# Oven_Control.net
KiCad netlist of a schematic drawn in EAGLE
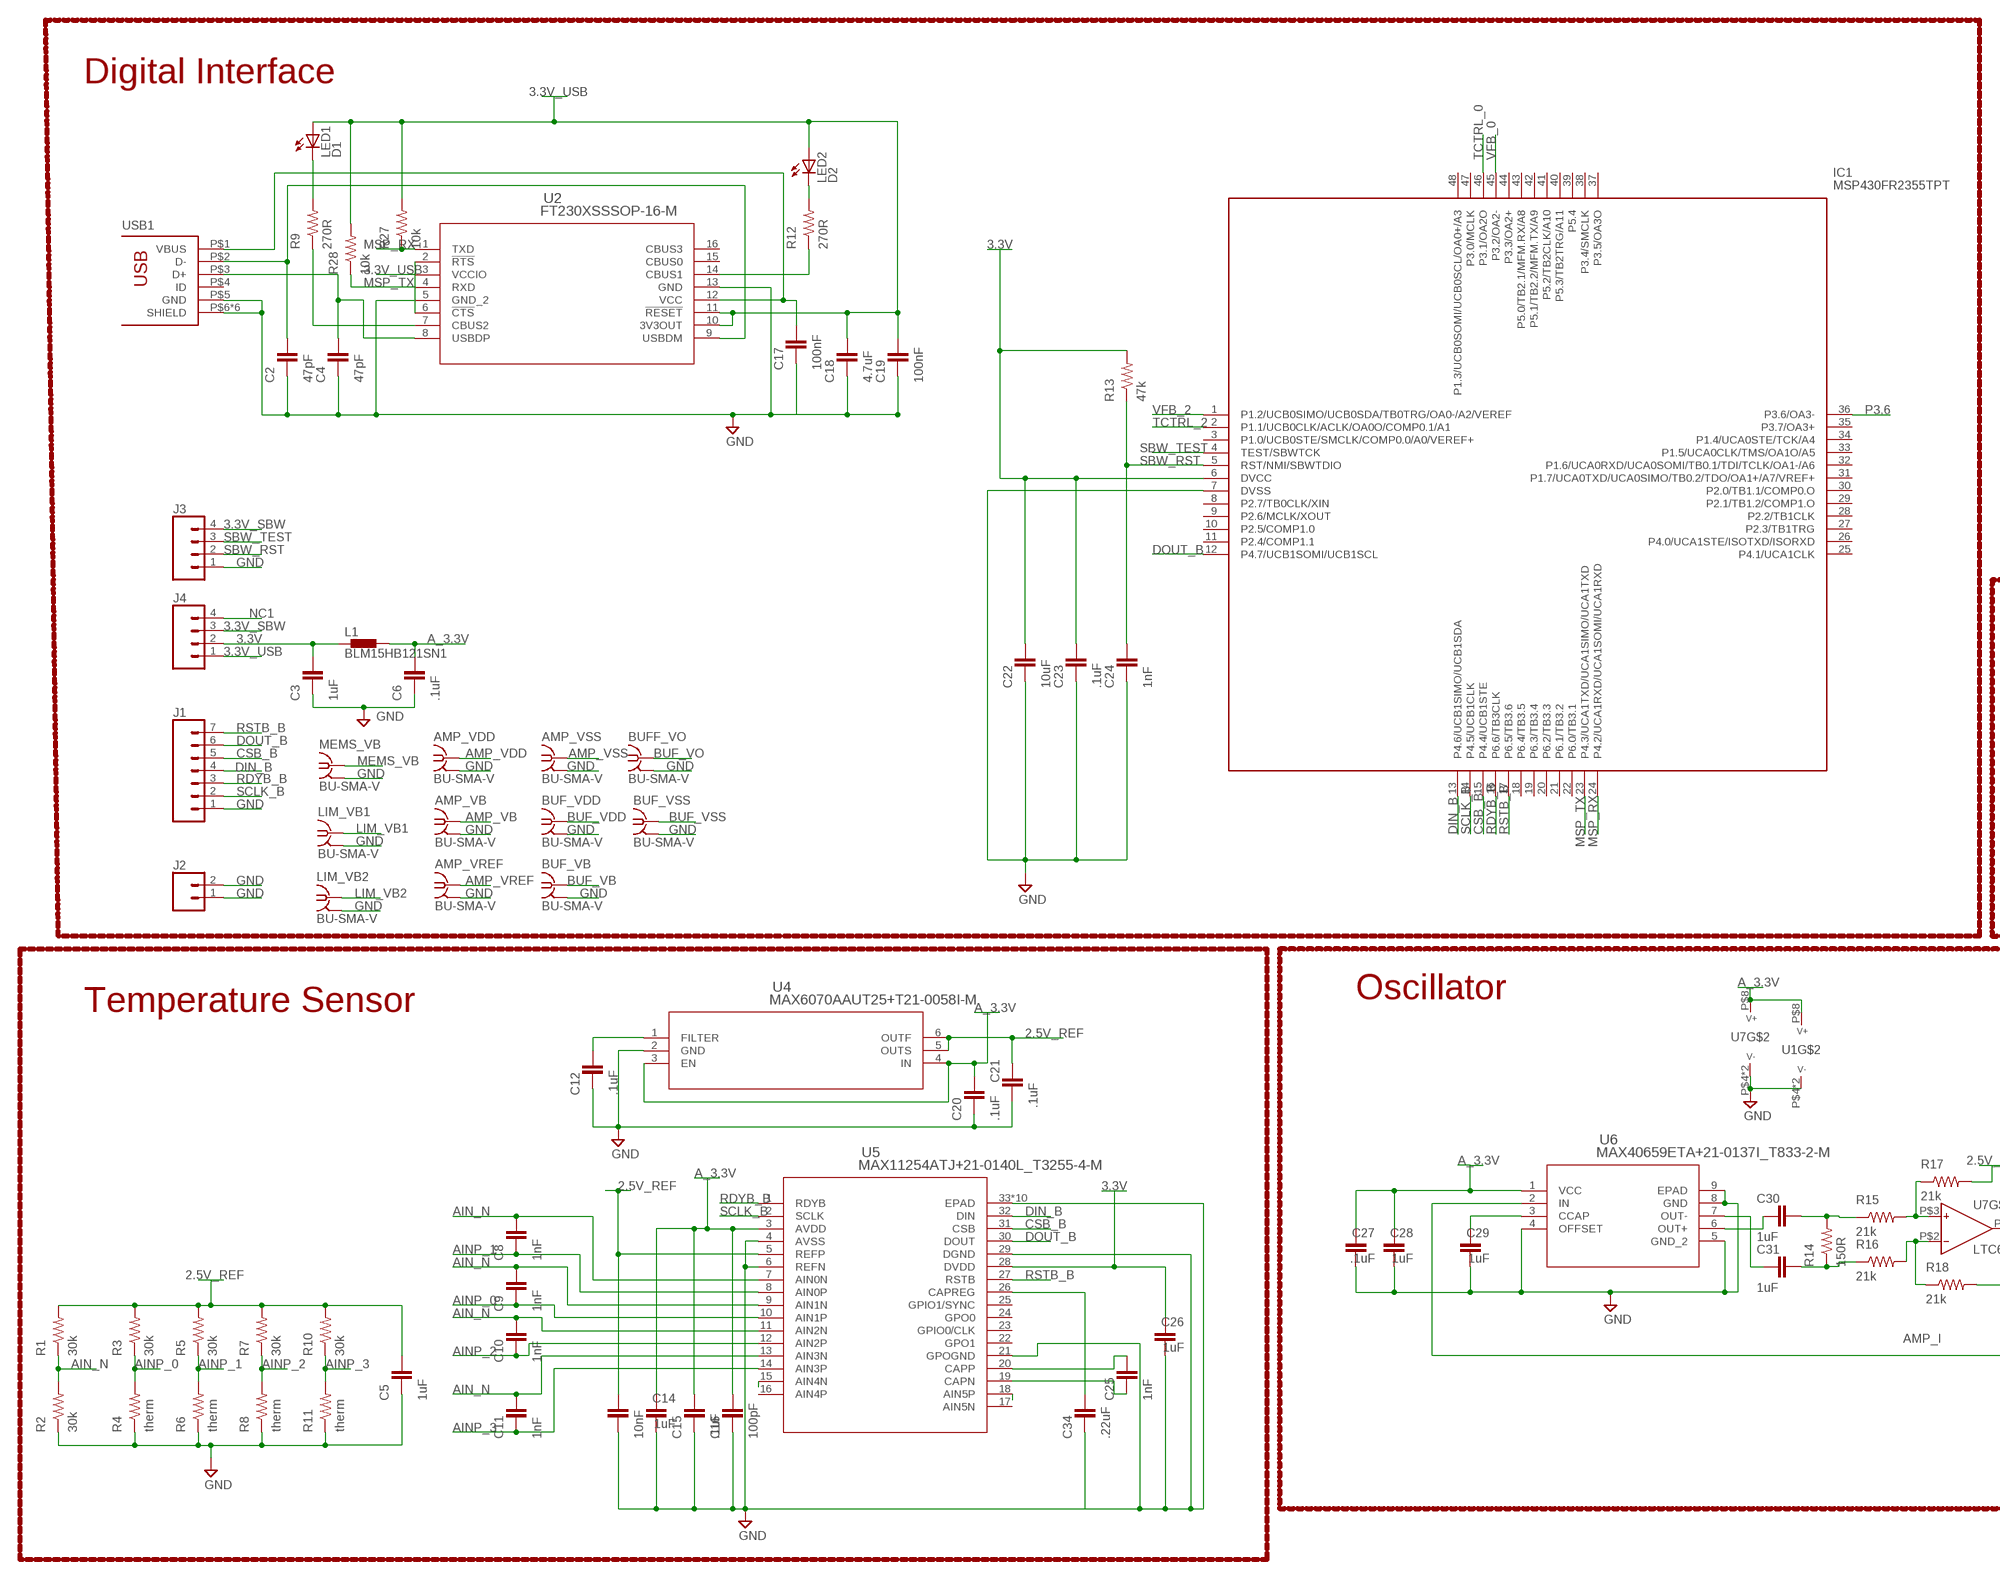
[diagram p0: schematic, sheet 1, part 1 of 2]
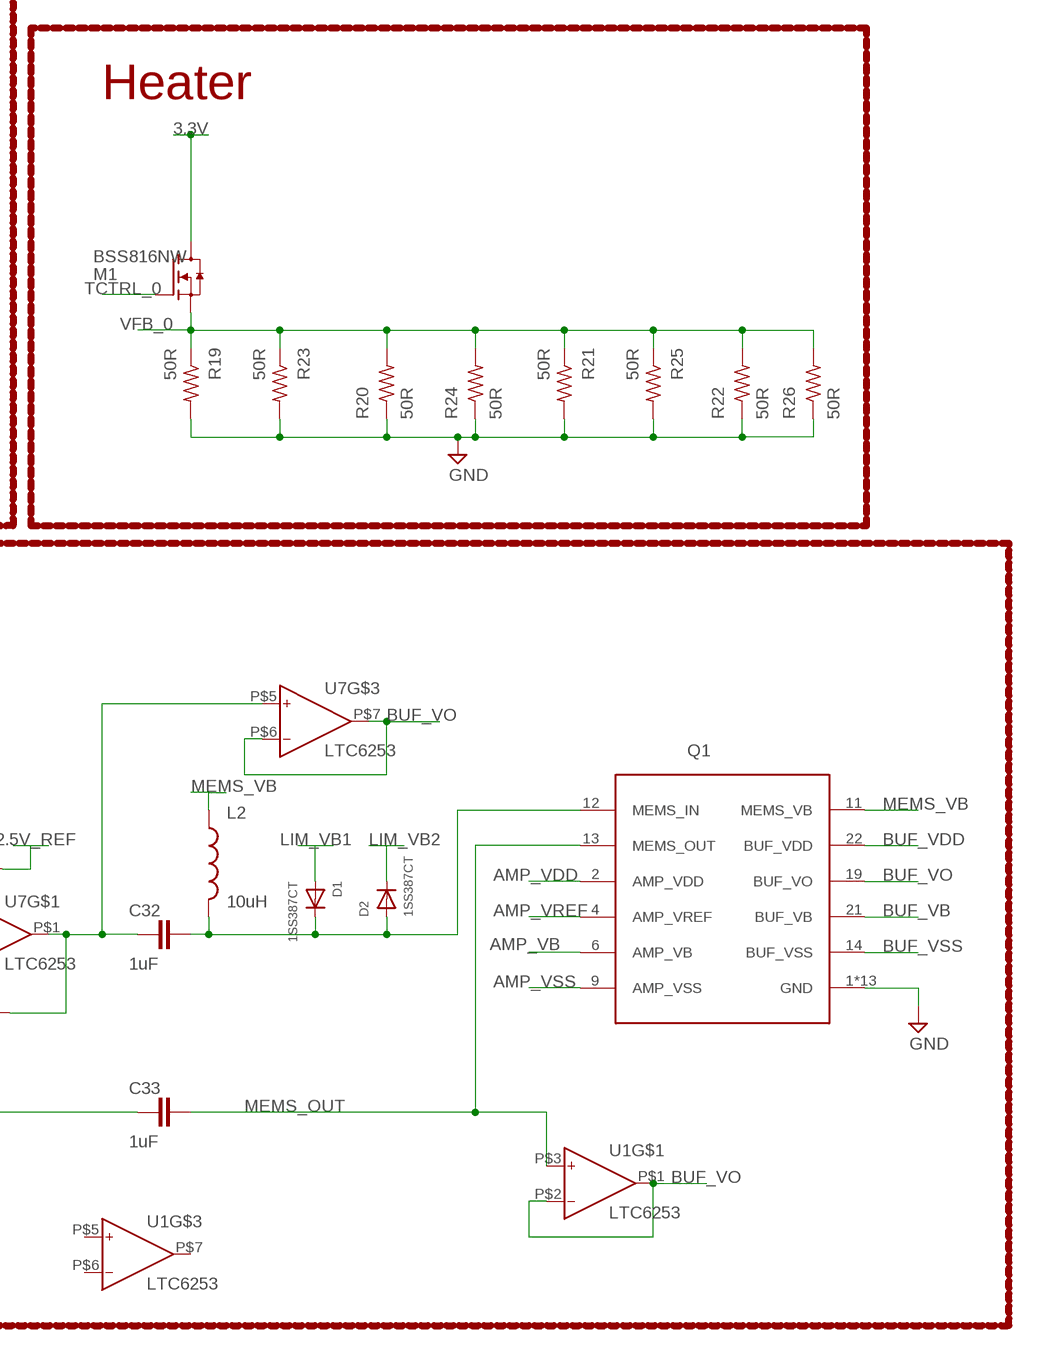
[diagram p1: schematic, sheet 1, part 2 of 2]

(export (version "E")
  (design (tool "Eeschema 10.0.6"))
  (components
    (comp (ref "AMP_VB")
      (value "BU-SMA-V")
      (footprint "eagle-import:BU-SMA-V")
      (libsource (lib "eagle-import") (part "BU-SMA-V"))
    )
    (comp (ref "AMP_VDD")
      (value "BU-SMA-V")
      (footprint "eagle-import:BU-SMA-V")
      (libsource (lib "eagle-import") (part "BU-SMA-V"))
    )
    (comp (ref "AMP_VREF")
      (value "BU-SMA-V")
      (footprint "eagle-import:BU-SMA-V")
      (libsource (lib "eagle-import") (part "BU-SMA-V"))
    )
    (comp (ref "AMP_VSS")
      (value "BU-SMA-V")
      (footprint "eagle-import:BU-SMA-V")
      (libsource (lib "eagle-import") (part "BU-SMA-V"))
    )
    (comp (ref "BUFF_VO")
      (value "BU-SMA-V")
      (footprint "eagle-import:BU-SMA-V")
      (libsource (lib "eagle-import") (part "BU-SMA-V"))
    )
    (comp (ref "BUF_VB")
      (value "BU-SMA-V")
      (footprint "eagle-import:BU-SMA-V")
      (libsource (lib "eagle-import") (part "BU-SMA-V"))
    )
    (comp (ref "BUF_VDD")
      (value "BU-SMA-V")
      (footprint "eagle-import:BU-SMA-V")
      (libsource (lib "eagle-import") (part "BU-SMA-V"))
    )
    (comp (ref "BUF_VSS")
      (value "BU-SMA-V")
      (footprint "eagle-import:BU-SMA-V")
      (libsource (lib "eagle-import") (part "BU-SMA-V"))
    )
    (comp (ref "C2")
      (value "47pF")
      (footprint "eagle-import:0402-CAP")
      (libsource (lib "eagle-import") (part "CAP0402-CAP"))
    )
    (comp (ref "C3")
      (value "1uF")
      (footprint "eagle-import:0402-CAP")
      (libsource (lib "eagle-import") (part "CAP0402-CAP"))
    )
    (comp (ref "C4")
      (value "47pF")
      (footprint "eagle-import:0402-CAP")
      (libsource (lib "eagle-import") (part "CAP0402-CAP"))
    )
    (comp (ref "C5")
      (value "1uF")
      (footprint "eagle-import:0402-CAP")
      (libsource (lib "eagle-import") (part "CAP0402-CAP"))
    )
    (comp (ref "C6")
      (value ".1uF")
      (footprint "eagle-import:0402-CAP")
      (libsource (lib "eagle-import") (part "CAP0402-CAP"))
    )
    (comp (ref "C8")
      (value "1nF")
      (footprint "eagle-import:0402-CAP")
      (libsource (lib "eagle-import") (part "CAP0402-CAP"))
    )
    (comp (ref "C9")
      (value "1nF")
      (footprint "eagle-import:0402-CAP")
      (libsource (lib "eagle-import") (part "CAP0402-CAP"))
    )
    (comp (ref "C10")
      (value "1nF")
      (footprint "eagle-import:0402-CAP")
      (libsource (lib "eagle-import") (part "CAP0402-CAP"))
    )
    (comp (ref "C11")
      (value "1nF")
      (footprint "eagle-import:0402-CAP")
      (libsource (lib "eagle-import") (part "CAP0402-CAP"))
    )
    (comp (ref "C12")
      (value ".1uF")
      (footprint "eagle-import:0402-CAP")
      (libsource (lib "eagle-import") (part "CAP0402-CAP"))
    )
    (comp (ref "C13")
      (value "10nF")
      (footprint "eagle-import:0402-CAP")
      (libsource (lib "eagle-import") (part "CAP0402-CAP"))
    )
    (comp (ref "C14")
      (value "1uF")
      (footprint "eagle-import:0402-CAP")
      (libsource (lib "eagle-import") (part "CAP0402-CAP"))
    )
    (comp (ref "C15")
      (value ".1uF")
      (footprint "eagle-import:0402-CAP")
      (libsource (lib "eagle-import") (part "CAP0402-CAP"))
    )
    (comp (ref "C16")
      (value "100pF")
      (footprint "eagle-import:0402-CAP")
      (libsource (lib "eagle-import") (part "CAP0402-CAP"))
    )
    (comp (ref "C17")
      (value "100nF")
      (footprint "eagle-import:0402-CAP")
      (libsource (lib "eagle-import") (part "CAP0402-CAP"))
    )
    (comp (ref "C18")
      (value "4.7uF")
      (footprint "eagle-import:0402-CAP")
      (libsource (lib "eagle-import") (part "CAP0402-CAP"))
    )
    (comp (ref "C19")
      (value "100nF")
      (footprint "eagle-import:0402-CAP")
      (libsource (lib "eagle-import") (part "CAP0402-CAP"))
    )
    (comp (ref "C20")
      (value ".1uF")
      (footprint "eagle-import:0402-CAP")
      (libsource (lib "eagle-import") (part "CAP0402-CAP"))
    )
    (comp (ref "C21")
      (value ".1uF")
      (footprint "eagle-import:0402-CAP")
      (libsource (lib "eagle-import") (part "CAP0402-CAP"))
    )
    (comp (ref "C22")
      (value "10uF")
      (footprint "eagle-import:0603-CAP")
      (libsource (lib "eagle-import") (part "CAP0603-CAP"))
    )
    (comp (ref "C23")
      (value ".1uF")
      (footprint "eagle-import:0402-CAP")
      (libsource (lib "eagle-import") (part "CAP0402-CAP"))
    )
    (comp (ref "C24")
      (value "1nF")
      (footprint "eagle-import:0402-CAP")
      (libsource (lib "eagle-import") (part "CAP0402-CAP"))
    )
    (comp (ref "C25")
      (value "1nF")
      (footprint "eagle-import:0402-CAP")
      (libsource (lib "eagle-import") (part "CAP0402-CAP"))
    )
    (comp (ref "C26")
      (value "1uF")
      (footprint "eagle-import:0402-CAP")
      (libsource (lib "eagle-import") (part "CAP0402-CAP"))
    )
    (comp (ref "C27")
      (value ".1uF")
      (footprint "eagle-import:0402-CAP")
      (libsource (lib "eagle-import") (part "CAP0402-CAP"))
    )
    (comp (ref "C28")
      (value "1uF")
      (footprint "eagle-import:0402-CAP")
      (libsource (lib "eagle-import") (part "CAP0402-CAP"))
    )
    (comp (ref "C29")
      (value "1uF")
      (footprint "eagle-import:0402-CAP")
      (libsource (lib "eagle-import") (part "CAP0402-CAP"))
    )
    (comp (ref "C30")
      (value "1uF")
      (footprint "eagle-import:0402-CAP")
      (libsource (lib "eagle-import") (part "CAP0402-CAP"))
    )
    (comp (ref "C31")
      (value "1uF")
      (footprint "eagle-import:0402-CAP")
      (libsource (lib "eagle-import") (part "CAP0402-CAP"))
    )
    (comp (ref "C32")
      (value "1uF")
      (footprint "eagle-import:0402-CAP")
      (libsource (lib "eagle-import") (part "CAP0402-CAP"))
    )
    (comp (ref "C33")
      (value "1uF")
      (footprint "eagle-import:0402-CAP")
      (libsource (lib "eagle-import") (part "CAP0402-CAP"))
    )
    (comp (ref "C34")
      (value ".22uF")
      (footprint "eagle-import:0402-CAP")
      (libsource (lib "eagle-import") (part "CAP0402-CAP"))
    )
    (comp (ref "D1")
      (value "1SS387CT")
      (footprint "eagle-import:SOD-882")
      (libsource (lib "eagle-import") (part "1SS387CT"))
    )
    (comp (ref "D2")
      (value "1SS387CT")
      (footprint "eagle-import:SOD-882")
      (libsource (lib "eagle-import") (part "1SS387CT"))
    )
    (comp (ref "IC1")
      (value "MSP430FR2355TPT")
      (footprint "eagle-import:QFP50P900X900X145-48N")
      (libsource (lib "eagle-import") (part "MSP430FR2355TPT"))
    )
    (comp (ref "J1")
      (value "CONN_07")
      (footprint "eagle-import:1X07")
      (libsource (lib "eagle-import") (part "CONN_07"))
    )
    (comp (ref "J2")
      (value "CONN_02")
      (footprint "eagle-import:1X02")
      (libsource (lib "eagle-import") (part "CONN_02"))
    )
    (comp (ref "J3")
      (value "CONN_04")
      (footprint "eagle-import:1X04")
      (libsource (lib "eagle-import") (part "CONN_04"))
    )
    (comp (ref "J4")
      (value "CONN_04")
      (footprint "eagle-import:1X04")
      (libsource (lib "eagle-import") (part "CONN_04"))
    )
    (comp (ref "L1")
      (value "BLM15HB121SN1")
      (footprint "eagle-import:0402")
      (libsource (lib "eagle-import") (part "BLM15HB121SN1"))
    )
    (comp (ref "L2")
      (value "10uH")
      (footprint "eagle-import:R0805")
      (libsource (lib "eagle-import") (part "INDUCTOR_0805"))
    )
    (comp (ref "LED1")
      (value "D1")
      (footprint "eagle-import:CHIPLED_0603")
      (libsource (lib "eagle-import") (part "LEDCHIPLED_0603"))
    )
    (comp (ref "LED2")
      (value "D2")
      (footprint "eagle-import:CHIPLED_0603")
      (libsource (lib "eagle-import") (part "LEDCHIPLED_0603"))
    )
    (comp (ref "LIM_VB1")
      (value "BU-SMA-V")
      (footprint "eagle-import:BU-SMA-V")
      (libsource (lib "eagle-import") (part "BU-SMA-V"))
    )
    (comp (ref "LIM_VB2")
      (value "BU-SMA-V")
      (footprint "eagle-import:BU-SMA-V")
      (libsource (lib "eagle-import") (part "BU-SMA-V"))
    )
    (comp (ref "M1")
      (value "BSS816NW")
      (footprint "eagle-import:SOT-323")
      (libsource (lib "eagle-import") (part "BSS816NW"))
    )
    (comp (ref "MEMS_VB")
      (value "BU-SMA-V")
      (footprint "eagle-import:BU-SMA-V")
      (libsource (lib "eagle-import") (part "BU-SMA-V"))
    )
    (comp (ref "Q1")
      (value "MEMS_RESONATOR")
      (footprint "eagle-import:DIL24")
      (libsource (lib "eagle-import") (part "MEMS_RESONATOR"))
    )
    (comp (ref "R1")
      (value "30k")
      (footprint "eagle-import:R0603")
      (fields (field (name "MANUFACTURER") "Rohm Semiconductor"))
      (libsource (lib "eagle-import") (part "R-US_R0603"))
    )
    (comp (ref "R2")
      (value "30k")
      (footprint "eagle-import:R0603")
      (fields (field (name "MANUFACTURER") "Rohm Semiconductor"))
      (libsource (lib "eagle-import") (part "R-US_R0603"))
    )
    (comp (ref "R3")
      (value "30k")
      (footprint "eagle-import:R0603")
      (fields (field (name "MANUFACTURER") "Rohm Semiconductor"))
      (libsource (lib "eagle-import") (part "R-US_R0603"))
    )
    (comp (ref "R4")
      (value "therm")
      (footprint "eagle-import:R0603")
      (fields (field (name "MANUFACTURER") "Rohm Semiconductor"))
      (libsource (lib "eagle-import") (part "R-US_R0603"))
    )
    (comp (ref "R5")
      (value "30k")
      (footprint "eagle-import:R0603")
      (fields (field (name "MANUFACTURER") "Rohm Semiconductor"))
      (libsource (lib "eagle-import") (part "R-US_R0603"))
    )
    (comp (ref "R6")
      (value "therm")
      (footprint "eagle-import:R0603")
      (fields (field (name "MANUFACTURER") "Rohm Semiconductor"))
      (libsource (lib "eagle-import") (part "R-US_R0603"))
    )
    (comp (ref "R7")
      (value "30k")
      (footprint "eagle-import:R0603")
      (fields (field (name "MANUFACTURER") "Rohm Semiconductor"))
      (libsource (lib "eagle-import") (part "R-US_R0603"))
    )
    (comp (ref "R8")
      (value "therm")
      (footprint "eagle-import:R0603")
      (fields (field (name "MANUFACTURER") "Rohm Semiconductor"))
      (libsource (lib "eagle-import") (part "R-US_R0603"))
    )
    (comp (ref "R9")
      (value "270R")
      (footprint "eagle-import:R0603")
      (fields (field (name "MANUFACTURER") "Rohm Semiconductor"))
      (libsource (lib "eagle-import") (part "R-US_R0603"))
    )
    (comp (ref "R10")
      (value "30k")
      (footprint "eagle-import:R0603")
      (fields (field (name "MANUFACTURER") "Rohm Semiconductor"))
      (libsource (lib "eagle-import") (part "R-US_R0603"))
    )
    (comp (ref "R11")
      (value "therm")
      (footprint "eagle-import:R0603")
      (fields (field (name "MANUFACTURER") "Rohm Semiconductor"))
      (libsource (lib "eagle-import") (part "R-US_R0603"))
    )
    (comp (ref "R12")
      (value "270R")
      (footprint "eagle-import:R0603")
      (fields (field (name "MANUFACTURER") "Rohm Semiconductor"))
      (libsource (lib "eagle-import") (part "R-US_R0603"))
    )
    (comp (ref "R13")
      (value "47k")
      (footprint "eagle-import:R0603")
      (fields (field (name "MANUFACTURER") "Rohm Semiconductor"))
      (libsource (lib "eagle-import") (part "R-US_R0603"))
    )
    (comp (ref "R14")
      (value "150R")
      (footprint "eagle-import:R0402")
      (libsource (lib "eagle-import") (part "R-US_R0402"))
    )
    (comp (ref "R15")
      (value "21k")
      (footprint "eagle-import:R0402")
      (libsource (lib "eagle-import") (part "R-US_R0402"))
    )
    (comp (ref "R16")
      (value "21k")
      (footprint "eagle-import:R0402")
      (libsource (lib "eagle-import") (part "R-US_R0402"))
    )
    (comp (ref "R17")
      (value "21k")
      (footprint "eagle-import:R0402")
      (libsource (lib "eagle-import") (part "R-US_R0402"))
    )
    (comp (ref "R18")
      (value "21k")
      (footprint "eagle-import:R0402")
      (libsource (lib "eagle-import") (part "R-US_R0402"))
    )
    (comp (ref "R19")
      (value "50R")
      (footprint "eagle-import:R1206")
      (libsource (lib "eagle-import") (part "R-US_R1206"))
    )
    (comp (ref "R20")
      (value "50R")
      (footprint "eagle-import:R1206")
      (libsource (lib "eagle-import") (part "R-US_R1206"))
    )
    (comp (ref "R21")
      (value "50R")
      (footprint "eagle-import:R1206")
      (libsource (lib "eagle-import") (part "R-US_R1206"))
    )
    (comp (ref "R22")
      (value "50R")
      (footprint "eagle-import:R1206")
      (libsource (lib "eagle-import") (part "R-US_R1206"))
    )
    (comp (ref "R23")
      (value "50R")
      (footprint "eagle-import:R1206")
      (libsource (lib "eagle-import") (part "R-US_R1206"))
    )
    (comp (ref "R24")
      (value "50R")
      (footprint "eagle-import:R1206")
      (libsource (lib "eagle-import") (part "R-US_R1206"))
    )
    (comp (ref "R25")
      (value "50R")
      (footprint "eagle-import:R1206")
      (libsource (lib "eagle-import") (part "R-US_R1206"))
    )
    (comp (ref "R26")
      (value "50R")
      (footprint "eagle-import:R1206")
      (libsource (lib "eagle-import") (part "R-US_R1206"))
    )
    (comp (ref "R27")
      (value "10k")
      (footprint "eagle-import:R0402")
      (libsource (lib "eagle-import") (part "R-US_R0402"))
    )
    (comp (ref "R28")
      (value "10k")
      (footprint "eagle-import:R0402")
      (libsource (lib "eagle-import") (part "R-US_R0402"))
    )
    (comp (ref "U1")
      (value "LTC6253")
      (footprint "eagle-import:DFN")
      (libsource (lib "eagle-import") (part "LTC6253"))
    )
    (comp (ref "U2")
      (value "FT230XSSSOP-16-M")
      (footprint "eagle-import:SSOP-16-M")
      (fields (field (name "MANUFACTURER_PART_NUMBER") "FT230XS"))
      (libsource (lib "eagle-import") (part "FT230XSSSOP-16-M"))
    )
    (comp (ref "U4")
      (value "MAX6070AAUT25+T21-0058I-M")
      (footprint "eagle-import:21-0058I-M")
      (fields (field (name "MANUFACTURER_PART_NUMBER") "MAX6070AAUT25+T"))
      (libsource (lib "eagle-import") (part "MAX6070AAUT25+T21-0058I-M"))
    )
    (comp (ref "U5")
      (value "MAX11254ATJ+21-0140L_T3255-4-M")
      (footprint "eagle-import:21-0140L_T3255-4-M")
      (fields (field (name "MANUFACTURER_PART_NUMBER") "MAX11254ATJ+"))
      (libsource (lib "eagle-import") (part "MAX11254ATJ+21-0140L_T3255-4-M"))
    )
    (comp (ref "U6")
      (value "MAX40659ETA+21-0137I_T833-2-M")
      (footprint "eagle-import:21-0137I_T833-2-M")
      (fields (field (name "MANUFACTURER_PART_NUMBER") "MAX40659ETA+"))
      (libsource (lib "eagle-import") (part "MAX40659ETA+21-0137I_T833-2-M"))
    )
    (comp (ref "U7")
      (value "LTC6253")
      (footprint "eagle-import:DFN")
      (fields (field (name "PART_NO") "LTC6253"))
      (libsource (lib "eagle-import") (part "LTC6253"))
    )
    (comp (ref "USB1")
      (value "USB-OTGMICRO-AB")
      (footprint "eagle-import:USB-MICRO-AB")
      (libsource (lib "eagle-import") (part "USB-OTGMICRO-AB"))
    )
  )
  (nets
    (net (code "1") (name "/2.5V_REF") (class "Default")
      (node (ref "C13") (pin "2") (pinfunction "2_2") (pintype "passive"))
      (node (ref "C21") (pin "2") (pinfunction "2_2") (pintype "passive"))
      (node (ref "C5") (pin "2") (pinfunction "2_2") (pintype "passive"))
      (node (ref "R1") (pin "2") (pinfunction "2_2") (pintype "passive"))
      (node (ref "R10") (pin "2") (pinfunction "2_2") (pintype "passive"))
      (node (ref "R17") (pin "2") (pinfunction "2_2") (pintype "passive"))
      (node (ref "R3") (pin "2") (pinfunction "2_2") (pintype "passive"))
      (node (ref "R5") (pin "2") (pinfunction "2_2") (pintype "passive"))
      (node (ref "R7") (pin "2") (pinfunction "2_2") (pintype "passive"))
      (node (ref "U4") (pin "5") (pinfunction "OUTS_5") (pintype "output"))
      (node (ref "U4") (pin "6") (pinfunction "OUTF_6") (pintype "output"))
      (node (ref "U5") (pin "5") (pinfunction "REFP_5") (pintype "passive"))
    )
    (net (code "2") (name "/3.3V") (class "Default")
      (node (ref "C22") (pin "2") (pinfunction "2_2") (pintype "passive"))
      (node (ref "C23") (pin "2") (pinfunction "2_2") (pintype "passive"))
      (node (ref "C26") (pin "2") (pinfunction "2_2") (pintype "passive"))
      (node (ref "C3") (pin "2") (pinfunction "2_2") (pintype "passive"))
      (node (ref "IC1") (pin "6") (pinfunction "DVCC_6") (pintype "bidirectional"))
      (node (ref "J4") (pin "2") (pinfunction "2_2") (pintype "passive"))
      (node (ref "L1") (pin "1") (pinfunction "1_1") (pintype "passive"))
      (node (ref "M1") (pin "D") (pinfunction "D_D") (pintype "passive"))
      (node (ref "R13") (pin "2") (pinfunction "2_2") (pintype "passive"))
      (node (ref "U5") (pin "28") (pinfunction "DVDD_28") (pintype "power_in"))
    )
    (net (code "3") (name "/3.3V_SBW") (class "Default")
      (node (ref "J3") (pin "4") (pinfunction "4_4") (pintype "passive"))
      (node (ref "J4") (pin "3") (pinfunction "3_3") (pintype "passive"))
    )
    (net (code "4") (name "/3.3V_USB") (class "Default")
      (node (ref "C18") (pin "2") (pinfunction "2_2") (pintype "passive"))
      (node (ref "C19") (pin "2") (pinfunction "2_2") (pintype "passive"))
      (node (ref "J4") (pin "1") (pinfunction "1_1") (pintype "passive"))
      (node (ref "LED1") (pin "A") (pinfunction "A_A") (pintype "passive"))
      (node (ref "LED2") (pin "A") (pinfunction "A_A") (pintype "passive"))
      (node (ref "R27") (pin "2") (pinfunction "2_2") (pintype "passive"))
      (node (ref "R28") (pin "2") (pinfunction "2_2") (pintype "passive"))
      (node (ref "U2") (pin "10") (pinfunction "3V3OUT_10") (pintype "power_in"))
      (node (ref "U2") (pin "11") (pinfunction "~{RESET}_11") (pintype "input"))
      (node (ref "U2") (pin "3") (pinfunction "VCCIO_3") (pintype "power_in"))
    )
    (net (code "5") (name "/AINP_0") (class "Default")
      (node (ref "C9") (pin "1") (pinfunction "1_1") (pintype "passive"))
      (node (ref "R3") (pin "1") (pinfunction "1_1") (pintype "passive"))
      (node (ref "R4") (pin "2") (pinfunction "2_2") (pintype "passive"))
      (node (ref "U5") (pin "10") (pinfunction "AIN1P_10") (pintype "input"))
    )
    (net (code "6") (name "/AINP_1") (class "Default")
      (node (ref "C8") (pin "1") (pinfunction "1_1") (pintype "passive"))
      (node (ref "R5") (pin "1") (pinfunction "1_1") (pintype "passive"))
      (node (ref "R6") (pin "2") (pinfunction "2_2") (pintype "passive"))
      (node (ref "U5") (pin "8") (pinfunction "AIN0P_8") (pintype "bidirectional"))
    )
    (net (code "7") (name "/AINP_2") (class "Default")
      (node (ref "C10") (pin "1") (pinfunction "1_1") (pintype "passive"))
      (node (ref "R7") (pin "1") (pinfunction "1_1") (pintype "passive"))
      (node (ref "R8") (pin "2") (pinfunction "2_2") (pintype "passive"))
      (node (ref "U5") (pin "12") (pinfunction "AIN2P_12") (pintype "input"))
    )
    (net (code "8") (name "/AINP_3") (class "Default")
      (node (ref "C11") (pin "1") (pinfunction "1_1") (pintype "passive"))
      (node (ref "R10") (pin "1") (pinfunction "1_1") (pintype "passive"))
      (node (ref "R11") (pin "2") (pinfunction "2_2") (pintype "passive"))
      (node (ref "U5") (pin "14") (pinfunction "AIN3P_14") (pintype "input"))
    )
    (net (code "9") (name "/AIN_N") (class "Default")
      (node (ref "C10") (pin "2") (pinfunction "2_2") (pintype "passive"))
      (node (ref "C11") (pin "2") (pinfunction "2_2") (pintype "passive"))
      (node (ref "C8") (pin "2") (pinfunction "2_2") (pintype "passive"))
      (node (ref "C9") (pin "2") (pinfunction "2_2") (pintype "passive"))
      (node (ref "R1") (pin "1") (pinfunction "1_1") (pintype "passive"))
      (node (ref "R2") (pin "2") (pinfunction "2_2") (pintype "passive"))
      (node (ref "U5") (pin "11") (pinfunction "AIN2N_11") (pintype "input"))
      (node (ref "U5") (pin "13") (pinfunction "AIN3N_13") (pintype "input"))
      (node (ref "U5") (pin "7") (pinfunction "AIN0N_7") (pintype "bidirectional"))
      (node (ref "U5") (pin "9") (pinfunction "AIN1N_9") (pintype "input"))
    )
    (net (code "10") (name "/AMP_I") (class "Default")
      (node (ref "C33") (pin "1") (pinfunction "1_1") (pintype "passive"))
      (node (ref "U6") (pin "2") (pinfunction "IN_2") (pintype "passive"))
    )
    (net (code "11") (name "/AMP_VB") (class "Default")
      (node (ref "AMP_VB") (pin "1") (pinfunction "1_1") (pintype "passive"))
      (node (ref "Q1") (pin "6") (pinfunction "AMP_VB_6") (pintype "bidirectional"))
    )
    (net (code "12") (name "/AMP_VDD") (class "Default")
      (node (ref "AMP_VDD") (pin "1") (pinfunction "1_1") (pintype "passive"))
      (node (ref "Q1") (pin "2") (pinfunction "AMP_VDD_2") (pintype "bidirectional"))
    )
    (net (code "13") (name "/AMP_VREF") (class "Default")
      (node (ref "AMP_VREF") (pin "1") (pinfunction "1_1") (pintype "passive"))
      (node (ref "Q1") (pin "4") (pinfunction "AMP_VREF_4") (pintype "bidirectional"))
    )
    (net (code "14") (name "/AMP_VSS") (class "Default")
      (node (ref "AMP_VSS") (pin "1") (pinfunction "1_1") (pintype "passive"))
      (node (ref "Q1") (pin "9") (pinfunction "AMP_VSS_9") (pintype "bidirectional"))
    )
    (net (code "15") (name "/A_3.3V") (class "Default")
      (node (ref "C14") (pin "2") (pinfunction "2_2") (pintype "passive"))
      (node (ref "C15") (pin "2") (pinfunction "2_2") (pintype "passive"))
      (node (ref "C16") (pin "2") (pinfunction "2_2") (pintype "passive"))
      (node (ref "C20") (pin "2") (pinfunction "2_2") (pintype "passive"))
      (node (ref "C27") (pin "2") (pinfunction "2_2") (pintype "passive"))
      (node (ref "C28") (pin "2") (pinfunction "2_2") (pintype "passive"))
      (node (ref "C6") (pin "2") (pinfunction "2_2") (pintype "passive"))
      (node (ref "L1") (pin "2") (pinfunction "2_2") (pintype "passive"))
      (node (ref "U1") (pin "P$8") (pinfunction "V+_P$8") (pintype "power_in"))
      (node (ref "U4") (pin "3") (pinfunction "EN_3") (pintype "passive"))
      (node (ref "U4") (pin "4") (pinfunction "IN_4") (pintype "input"))
      (node (ref "U5") (pin "3") (pinfunction "AVDD_3") (pintype "power_in"))
      (node (ref "U6") (pin "1") (pinfunction "VCC_1") (pintype "power_in"))
      (node (ref "U7") (pin "P$8") (pinfunction "V+_P$8") (pintype "power_in"))
    )
    (net (code "16") (name "/BUF_VB") (class "Default")
      (node (ref "BUF_VB") (pin "1") (pinfunction "1_1") (pintype "passive"))
      (node (ref "Q1") (pin "21") (pinfunction "BUF_VB_21") (pintype "bidirectional"))
    )
    (net (code "17") (name "/BUF_VDD") (class "Default")
      (node (ref "BUF_VDD") (pin "1") (pinfunction "1_1") (pintype "passive"))
      (node (ref "Q1") (pin "22") (pinfunction "BUF_VDD_22") (pintype "bidirectional"))
    )
    (net (code "18") (name "/BUF_VO") (class "Default")
      (node (ref "BUFF_VO") (pin "1") (pinfunction "1_1") (pintype "passive"))
      (node (ref "Q1") (pin "19") (pinfunction "BUF_VO_19") (pintype "bidirectional"))
      (node (ref "U1") (pin "P$1") (pinfunction "OUT_P$1") (pintype "output"))
      (node (ref "U1") (pin "P$2") (pinfunction "IN-_P$2") (pintype "input"))
      (node (ref "U7") (pin "P$6") (pinfunction "IN-_P$6") (pintype "input"))
      (node (ref "U7") (pin "P$7") (pinfunction "OUT_P$7") (pintype "output"))
    )
    (net (code "19") (name "/BUF_VSS") (class "Default")
      (node (ref "BUF_VSS") (pin "1") (pinfunction "1_1") (pintype "passive"))
      (node (ref "Q1") (pin "14") (pinfunction "BUF_VSS_14") (pintype "bidirectional"))
    )
    (net (code "20") (name "/CSB_B") (class "Default")
      (node (ref "IC1") (pin "15") (pinfunction "P4.4/UCB1STE_15") (pintype "bidirectional"))
      (node (ref "J1") (pin "5") (pinfunction "5_5") (pintype "passive"))
      (node (ref "U5") (pin "31") (pinfunction "CSB_31") (pintype "passive"))
    )
    (net (code "21") (name "/DIN_B") (class "Default")
      (node (ref "IC1") (pin "13") (pinfunction "P4.6/UCB1SIMO/UCB1SDA_13") (pintype "bidirectional"))
      (node (ref "J1") (pin "4") (pinfunction "4_4") (pintype "passive"))
      (node (ref "U5") (pin "32") (pinfunction "DIN_32") (pintype "passive"))
    )
    (net (code "22") (name "/DOUT_B") (class "Default")
      (node (ref "IC1") (pin "12") (pinfunction "P4.7/UCB1SOMI/UCB1SCL_12") (pintype "bidirectional"))
      (node (ref "J1") (pin "6") (pinfunction "6_6") (pintype "passive"))
      (node (ref "U5") (pin "30") (pinfunction "DOUT_30") (pintype "output"))
    )
    (net (code "23") (name "/LIM_VB1") (class "Default")
      (node (ref "D1") (pin "A") (pinfunction "A_A") (pintype "passive"))
      (node (ref "LIM_VB1") (pin "1") (pinfunction "1_1") (pintype "passive"))
    )
    (net (code "24") (name "/LIM_VB2") (class "Default")
      (node (ref "D2") (pin "C") (pinfunction "C_C") (pintype "passive"))
      (node (ref "LIM_VB2") (pin "1") (pinfunction "1_1") (pintype "passive"))
    )
    (net (code "25") (name "/MEMS_OUT") (class "Default")
      (node (ref "C33") (pin "2") (pinfunction "2_2") (pintype "passive"))
      (node (ref "Q1") (pin "13") (pinfunction "MEMS_OUT_13") (pintype "bidirectional"))
      (node (ref "U1") (pin "P$3") (pinfunction "IN+_P$3") (pintype "input"))
    )
    (net (code "26") (name "/MEMS_VB") (class "Default")
      (node (ref "L2") (pin "1") (pinfunction "1_1") (pintype "passive"))
      (node (ref "MEMS_VB") (pin "1") (pinfunction "1_1") (pintype "passive"))
      (node (ref "Q1") (pin "11") (pinfunction "MEMS_VB_11") (pintype "bidirectional"))
    )
    (net (code "27") (name "/MSP_RX") (class "Default")
      (node (ref "IC1") (pin "24") (pinfunction "P4.2/UCA1RXD/UCA1SOMI/UCA1RXD_24") (pintype "bidirectional"))
      (node (ref "R27") (pin "1") (pinfunction "1_1") (pintype "passive"))
      (node (ref "U2") (pin "1") (pinfunction "TXD_1") (pintype "output"))
    )
    (net (code "28") (name "/MSP_TX") (class "Default")
      (node (ref "IC1") (pin "23") (pinfunction "P4.3/UCA1TXD/UCA1SIMO/UCA1TXD_23") (pintype "bidirectional"))
      (node (ref "R28") (pin "1") (pinfunction "1_1") (pintype "passive"))
      (node (ref "U2") (pin "4") (pinfunction "RXD_4") (pintype "input"))
    )
    (net (code "29") (name "/NC1") (class "Default")
      (node (ref "J4") (pin "4") (pinfunction "4_4") (pintype "passive"))
    )
    (net (code "30") (name "/P3.6") (class "Default")
      (node (ref "IC1") (pin "36") (pinfunction "P3.6/OA3-_36") (pintype "bidirectional"))
    )
    (net (code "31") (name "/RDYB_B") (class "Default")
      (node (ref "IC1") (pin "16") (pinfunction "P6.6/TB3CLK_16") (pintype "bidirectional"))
      (node (ref "J1") (pin "3") (pinfunction "3_3") (pintype "passive"))
      (node (ref "U5") (pin "1") (pinfunction "RDYB_1") (pintype "passive"))
    )
    (net (code "32") (name "/RSTB_B") (class "Default")
      (node (ref "IC1") (pin "17") (pinfunction "P6.5/TB3.6_17") (pintype "bidirectional"))
      (node (ref "J1") (pin "7") (pinfunction "7_7") (pintype "passive"))
      (node (ref "U5") (pin "27") (pinfunction "RSTB_27") (pintype "passive"))
    )
    (net (code "33") (name "/SBW_RST") (class "Default")
      (node (ref "C24") (pin "2") (pinfunction "2_2") (pintype "passive"))
      (node (ref "IC1") (pin "5") (pinfunction "RST/NMI/SBWTDIO_5") (pintype "bidirectional"))
      (node (ref "J3") (pin "2") (pinfunction "2_2") (pintype "passive"))
      (node (ref "R13") (pin "1") (pinfunction "1_1") (pintype "passive"))
    )
    (net (code "34") (name "/SBW_TEST") (class "Default")
      (node (ref "IC1") (pin "4") (pinfunction "TEST/SBWTCK_4") (pintype "bidirectional"))
      (node (ref "J3") (pin "3") (pinfunction "3_3") (pintype "passive"))
    )
    (net (code "35") (name "/SCLK_B") (class "Default")
      (node (ref "IC1") (pin "14") (pinfunction "P4.5/UCB1CLK_14") (pintype "bidirectional"))
      (node (ref "J1") (pin "2") (pinfunction "2_2") (pintype "passive"))
      (node (ref "U5") (pin "2") (pinfunction "SCLK_2") (pintype "passive"))
    )
    (net (code "36") (name "/TCTRL_0") (class "Default")
      (node (ref "IC1") (pin "46") (pinfunction "P3.1/OA2O_46") (pintype "bidirectional"))
      (node (ref "M1") (pin "G") (pinfunction "G_G") (pintype "passive"))
    )
    (net (code "37") (name "/TCTRL_2") (class "Default")
      (node (ref "IC1") (pin "2") (pinfunction "P1.1/UCB0CLK/ACLK/OA0O/COMP0.1/A1_2") (pintype "bidirectional"))
    )
    (net (code "38") (name "/VFB_0") (class "Default")
      (node (ref "IC1") (pin "45") (pinfunction "P3.2/OA2-_45") (pintype "bidirectional"))
      (node (ref "M1") (pin "S") (pinfunction "S_S") (pintype "passive"))
      (node (ref "R19") (pin "1") (pinfunction "1_1") (pintype "passive"))
      (node (ref "R20") (pin "2") (pinfunction "2_2") (pintype "passive"))
      (node (ref "R21") (pin "1") (pinfunction "1_1") (pintype "passive"))
      (node (ref "R22") (pin "2") (pinfunction "2_2") (pintype "passive"))
      (node (ref "R23") (pin "1") (pinfunction "1_1") (pintype "passive"))
      (node (ref "R24") (pin "2") (pinfunction "2_2") (pintype "passive"))
      (node (ref "R25") (pin "1") (pinfunction "1_1") (pintype "passive"))
      (node (ref "R26") (pin "2") (pinfunction "2_2") (pintype "passive"))
    )
    (net (code "39") (name "/VFB_2") (class "Default")
      (node (ref "IC1") (pin "1") (pinfunction "P1.2/UCB0SIMO/UCB0SDA/TB0TRG/OA0-/A2/VEREF_1") (pintype "bidirectional"))
    )
    (net (code "40") (name "GND") (class "Default")
      (node (ref "AMP_VB") (pin "2") (pinfunction "2_2") (pintype "passive"))
      (node (ref "AMP_VB") (pin "3") (pinfunction "2_3") (pintype "passive"))
      (node (ref "AMP_VB") (pin "4") (pinfunction "2_4") (pintype "passive"))
      (node (ref "AMP_VB") (pin "5") (pinfunction "2_5") (pintype "passive"))
      (node (ref "AMP_VDD") (pin "2") (pinfunction "2_2") (pintype "passive"))
      (node (ref "AMP_VDD") (pin "3") (pinfunction "2_3") (pintype "passive"))
      (node (ref "AMP_VDD") (pin "4") (pinfunction "2_4") (pintype "passive"))
      (node (ref "AMP_VDD") (pin "5") (pinfunction "2_5") (pintype "passive"))
      (node (ref "AMP_VREF") (pin "2") (pinfunction "2_2") (pintype "passive"))
      (node (ref "AMP_VREF") (pin "3") (pinfunction "2_3") (pintype "passive"))
      (node (ref "AMP_VREF") (pin "4") (pinfunction "2_4") (pintype "passive"))
      (node (ref "AMP_VREF") (pin "5") (pinfunction "2_5") (pintype "passive"))
      (node (ref "AMP_VSS") (pin "2") (pinfunction "2_2") (pintype "passive"))
      (node (ref "AMP_VSS") (pin "3") (pinfunction "2_3") (pintype "passive"))
      (node (ref "AMP_VSS") (pin "4") (pinfunction "2_4") (pintype "passive"))
      (node (ref "AMP_VSS") (pin "5") (pinfunction "2_5") (pintype "passive"))
      (node (ref "BUFF_VO") (pin "2") (pinfunction "2_2") (pintype "passive"))
      (node (ref "BUFF_VO") (pin "3") (pinfunction "2_3") (pintype "passive"))
      (node (ref "BUFF_VO") (pin "4") (pinfunction "2_4") (pintype "passive"))
      (node (ref "BUFF_VO") (pin "5") (pinfunction "2_5") (pintype "passive"))
      (node (ref "BUF_VB") (pin "2") (pinfunction "2_2") (pintype "passive"))
      (node (ref "BUF_VB") (pin "3") (pinfunction "2_3") (pintype "passive"))
      (node (ref "BUF_VB") (pin "4") (pinfunction "2_4") (pintype "passive"))
      (node (ref "BUF_VB") (pin "5") (pinfunction "2_5") (pintype "passive"))
      (node (ref "BUF_VDD") (pin "2") (pinfunction "2_2") (pintype "passive"))
      (node (ref "BUF_VDD") (pin "3") (pinfunction "2_3") (pintype "passive"))
      (node (ref "BUF_VDD") (pin "4") (pinfunction "2_4") (pintype "passive"))
      (node (ref "BUF_VDD") (pin "5") (pinfunction "2_5") (pintype "passive"))
      (node (ref "BUF_VSS") (pin "2") (pinfunction "2_2") (pintype "passive"))
      (node (ref "BUF_VSS") (pin "3") (pinfunction "2_3") (pintype "passive"))
      (node (ref "BUF_VSS") (pin "4") (pinfunction "2_4") (pintype "passive"))
      (node (ref "BUF_VSS") (pin "5") (pinfunction "2_5") (pintype "passive"))
      (node (ref "C12") (pin "1") (pinfunction "1_1") (pintype "passive"))
      (node (ref "C13") (pin "1") (pinfunction "1_1") (pintype "passive"))
      (node (ref "C14") (pin "1") (pinfunction "1_1") (pintype "passive"))
      (node (ref "C15") (pin "1") (pinfunction "1_1") (pintype "passive"))
      (node (ref "C16") (pin "1") (pinfunction "1_1") (pintype "passive"))
      (node (ref "C17") (pin "1") (pinfunction "1_1") (pintype "passive"))
      (node (ref "C18") (pin "1") (pinfunction "1_1") (pintype "passive"))
      (node (ref "C19") (pin "1") (pinfunction "1_1") (pintype "passive"))
      (node (ref "C2") (pin "1") (pinfunction "1_1") (pintype "passive"))
      (node (ref "C20") (pin "1") (pinfunction "1_1") (pintype "passive"))
      (node (ref "C21") (pin "1") (pinfunction "1_1") (pintype "passive"))
      (node (ref "C22") (pin "1") (pinfunction "1_1") (pintype "passive"))
      (node (ref "C23") (pin "1") (pinfunction "1_1") (pintype "passive"))
      (node (ref "C24") (pin "1") (pinfunction "1_1") (pintype "passive"))
      (node (ref "C26") (pin "1") (pinfunction "1_1") (pintype "passive"))
      (node (ref "C27") (pin "1") (pinfunction "1_1") (pintype "passive"))
      (node (ref "C28") (pin "1") (pinfunction "1_1") (pintype "passive"))
      (node (ref "C29") (pin "1") (pinfunction "1_1") (pintype "passive"))
      (node (ref "C3") (pin "1") (pinfunction "1_1") (pintype "passive"))
      (node (ref "C34") (pin "1") (pinfunction "1_1") (pintype "passive"))
      (node (ref "C4") (pin "1") (pinfunction "1_1") (pintype "passive"))
      (node (ref "C5") (pin "1") (pinfunction "1_1") (pintype "passive"))
      (node (ref "C6") (pin "1") (pinfunction "1_1") (pintype "passive"))
      (node (ref "IC1") (pin "7") (pinfunction "DVSS_7") (pintype "bidirectional"))
      (node (ref "J1") (pin "1") (pinfunction "1_1") (pintype "passive"))
      (node (ref "J2") (pin "1") (pinfunction "1_1") (pintype "passive"))
      (node (ref "J2") (pin "2") (pinfunction "2_2") (pintype "passive"))
      (node (ref "J3") (pin "1") (pinfunction "1_1") (pintype "passive"))
      (node (ref "LIM_VB1") (pin "2") (pinfunction "2_2") (pintype "passive"))
      (node (ref "LIM_VB1") (pin "3") (pinfunction "2_3") (pintype "passive"))
      (node (ref "LIM_VB1") (pin "4") (pinfunction "2_4") (pintype "passive"))
      (node (ref "LIM_VB1") (pin "5") (pinfunction "2_5") (pintype "passive"))
      (node (ref "LIM_VB2") (pin "2") (pinfunction "2_2") (pintype "passive"))
      (node (ref "LIM_VB2") (pin "3") (pinfunction "2_3") (pintype "passive"))
      (node (ref "LIM_VB2") (pin "4") (pinfunction "2_4") (pintype "passive"))
      (node (ref "LIM_VB2") (pin "5") (pinfunction "2_5") (pintype "passive"))
      (node (ref "MEMS_VB") (pin "2") (pinfunction "2_2") (pintype "passive"))
      (node (ref "MEMS_VB") (pin "3") (pinfunction "2_3") (pintype "passive"))
      (node (ref "MEMS_VB") (pin "4") (pinfunction "2_4") (pintype "passive"))
      (node (ref "MEMS_VB") (pin "5") (pinfunction "2_5") (pintype "passive"))
      (node (ref "Q1") (pin "1") (pinfunction "GND_1") (pintype "bidirectional"))
      (node (ref "Q1") (pin "10") (pinfunction "GND_10") (pintype "bidirectional"))
      (node (ref "Q1") (pin "15") (pinfunction "GND_15") (pintype "bidirectional"))
      (node (ref "Q1") (pin "16") (pinfunction "GND_16") (pintype "bidirectional"))
      (node (ref "Q1") (pin "17") (pinfunction "GND_17") (pintype "bidirectional"))
      (node (ref "Q1") (pin "18") (pinfunction "GND_18") (pintype "bidirectional"))
      (node (ref "Q1") (pin "20") (pinfunction "GND_20") (pintype "bidirectional"))
      (node (ref "Q1") (pin "23") (pinfunction "GND_23") (pintype "bidirectional"))
      (node (ref "Q1") (pin "24") (pinfunction "GND_24") (pintype "bidirectional"))
      (node (ref "Q1") (pin "3") (pinfunction "GND_3") (pintype "bidirectional"))
      (node (ref "Q1") (pin "5") (pinfunction "GND_5") (pintype "bidirectional"))
      (node (ref "Q1") (pin "7") (pinfunction "GND_7") (pintype "bidirectional"))
      (node (ref "Q1") (pin "8") (pinfunction "GND_8") (pintype "bidirectional"))
      (node (ref "R11") (pin "1") (pinfunction "1_1") (pintype "passive"))
      (node (ref "R19") (pin "2") (pinfunction "2_2") (pintype "passive"))
      (node (ref "R2") (pin "1") (pinfunction "1_1") (pintype "passive"))
      (node (ref "R20") (pin "1") (pinfunction "1_1") (pintype "passive"))
      (node (ref "R21") (pin "2") (pinfunction "2_2") (pintype "passive"))
      (node (ref "R22") (pin "1") (pinfunction "1_1") (pintype "passive"))
      (node (ref "R23") (pin "2") (pinfunction "2_2") (pintype "passive"))
      (node (ref "R24") (pin "1") (pinfunction "1_1") (pintype "passive"))
      (node (ref "R25") (pin "2") (pinfunction "2_2") (pintype "passive"))
      (node (ref "R26") (pin "1") (pinfunction "1_1") (pintype "passive"))
      (node (ref "R4") (pin "1") (pinfunction "1_1") (pintype "passive"))
      (node (ref "R6") (pin "1") (pinfunction "1_1") (pintype "passive"))
      (node (ref "R8") (pin "1") (pinfunction "1_1") (pintype "passive"))
      (node (ref "U1") (pin "P$4") (pinfunction "V-_P$4") (pintype "power_in"))
      (node (ref "U1") (pin "P$9") (pinfunction "V-_P$9") (pintype "power_in"))
      (node (ref "U2") (pin "13") (pinfunction "GND_13") (pintype "power_in"))
      (node (ref "U2") (pin "5") (pinfunction "GND_2_5") (pintype "power_in"))
      (node (ref "U4") (pin "2") (pinfunction "GND_2") (pintype "power_in"))
      (node (ref "U5") (pin "21") (pinfunction "GPOGND_21") (pintype "passive"))
      (node (ref "U5") (pin "29") (pinfunction "DGND_29") (pintype "passive"))
      (node (ref "U5") (pin "33") (pinfunction "EPAD_33") (pintype "passive"))
      (node (ref "U5") (pin "4") (pinfunction "AVSS_4") (pintype "passive"))
      (node (ref "U5") (pin "6") (pinfunction "REFN_6") (pintype "passive"))
      (node (ref "U5") (pin "P$1") (pinfunction "EPAD_P$1") (pintype "passive"))
      (node (ref "U5") (pin "P$2") (pinfunction "EPAD_P$2") (pintype "passive"))
      (node (ref "U5") (pin "P$3") (pinfunction "EPAD_P$3") (pintype "passive"))
      (node (ref "U5") (pin "P$4") (pinfunction "EPAD_P$4") (pintype "passive"))
      (node (ref "U5") (pin "P$5") (pinfunction "EPAD_P$5") (pintype "passive"))
      (node (ref "U5") (pin "P$6") (pinfunction "EPAD_P$6") (pintype "passive"))
      (node (ref "U5") (pin "P$7") (pinfunction "EPAD_P$7") (pintype "passive"))
      (node (ref "U5") (pin "P$8") (pinfunction "EPAD_P$8") (pintype "passive"))
      (node (ref "U5") (pin "P$9") (pinfunction "EPAD_P$9") (pintype "passive"))
      (node (ref "U6") (pin "4") (pinfunction "OFFSET_4") (pintype "passive"))
      (node (ref "U6") (pin "5") (pinfunction "GND_2_5") (pintype "passive"))
      (node (ref "U6") (pin "8") (pinfunction "GND_8") (pintype "passive"))
      (node (ref "U6") (pin "9") (pinfunction "EPAD_9") (pintype "passive"))
      (node (ref "U7") (pin "P$4") (pinfunction "V-_P$4") (pintype "power_in"))
      (node (ref "U7") (pin "P$9") (pinfunction "V-_P$9") (pintype "power_in"))
      (node (ref "USB1") (pin "P$10") (pinfunction "SHIELD_P$10") (pintype "bidirectional"))
      (node (ref "USB1") (pin "P$11") (pinfunction "SHIELD_P$11") (pintype "bidirectional"))
      (node (ref "USB1") (pin "P$5") (pinfunction "GND_P$5") (pintype "bidirectional"))
      (node (ref "USB1") (pin "P$6") (pinfunction "SHIELD_P$6") (pintype "bidirectional"))
      (node (ref "USB1") (pin "P$7") (pinfunction "SHIELD_P$7") (pintype "bidirectional"))
      (node (ref "USB1") (pin "P$8") (pinfunction "SHIELD_P$8") (pintype "bidirectional"))
      (node (ref "USB1") (pin "P$9") (pinfunction "SHIELD_P$9") (pintype "bidirectional"))
    )
    (net (code "41") (name "Net-(C30-Pad2)") (class "Default")
      (node (ref "C30") (pin "2") (pinfunction "2_2") (pintype "passive"))
      (node (ref "R14") (pin "2") (pinfunction "2_2") (pintype "passive"))
      (node (ref "R15") (pin "1") (pinfunction "1_1") (pintype "passive"))
    )
    (net (code "42") (name "Net-(C31-Pad2)") (class "Default")
      (node (ref "C31") (pin "2") (pinfunction "2_2") (pintype "passive"))
      (node (ref "R14") (pin "1") (pinfunction "1_1") (pintype "passive"))
      (node (ref "R16") (pin "1") (pinfunction "1_1") (pintype "passive"))
    )
    (net (code "43") (name "Net-(LED1-PadC)") (class "Default")
      (node (ref "LED1") (pin "C") (pinfunction "C_C") (pintype "passive"))
      (node (ref "R9") (pin "2") (pinfunction "2_2") (pintype "passive"))
    )
    (net (code "44") (name "Net-(LED2-PadC)") (class "Default")
      (node (ref "LED2") (pin "C") (pinfunction "C_C") (pintype "passive"))
      (node (ref "R12") (pin "2") (pinfunction "2_2") (pintype "passive"))
    )
    (net (code "45") (name "Net-(Q1-MEMS_IN)") (class "Default")
      (node (ref "C32") (pin "2") (pinfunction "2_2") (pintype "passive"))
      (node (ref "D1") (pin "C") (pinfunction "C_C") (pintype "passive"))
      (node (ref "D2") (pin "A") (pinfunction "A_A") (pintype "passive"))
      (node (ref "L2") (pin "2") (pinfunction "2_2") (pintype "passive"))
      (node (ref "Q1") (pin "12") (pinfunction "MEMS_IN_12") (pintype "bidirectional"))
    )
    (net (code "46") (name "Net-(U2-CBUS1)") (class "Default")
      (node (ref "R12") (pin "1") (pinfunction "1_1") (pintype "passive"))
      (node (ref "U2") (pin "14") (pinfunction "CBUS1_14") (pintype "bidirectional"))
    )
    (net (code "47") (name "Net-(U2-CBUS2)") (class "Default")
      (node (ref "R9") (pin "1") (pinfunction "1_1") (pintype "passive"))
      (node (ref "U2") (pin "7") (pinfunction "CBUS2_7") (pintype "bidirectional"))
    )
    (net (code "48") (name "Net-(U2-USBDM)") (class "Default")
      (node (ref "C2") (pin "2") (pinfunction "2_2") (pintype "passive"))
      (node (ref "U2") (pin "9") (pinfunction "USBDM_9") (pintype "input"))
      (node (ref "USB1") (pin "P$2") (pinfunction "D-_P$2") (pintype "bidirectional"))
    )
    (net (code "49") (name "Net-(U2-USBDP)") (class "Default")
      (node (ref "C4") (pin "2") (pinfunction "2_2") (pintype "passive"))
      (node (ref "U2") (pin "8") (pinfunction "USBDP_8") (pintype "input"))
      (node (ref "USB1") (pin "P$3") (pinfunction "D+_P$3") (pintype "bidirectional"))
    )
    (net (code "50") (name "Net-(U2-VCC)") (class "Default")
      (node (ref "C17") (pin "2") (pinfunction "2_2") (pintype "passive"))
      (node (ref "U2") (pin "12") (pinfunction "VCC_12") (pintype "power_in"))
      (node (ref "USB1") (pin "P$1") (pinfunction "VBUS_P$1") (pintype "bidirectional"))
    )
    (net (code "51") (name "Net-(U2-~{CTS})") (class "Default")
      (node (ref "U2") (pin "2") (pinfunction "~{RTS}_2") (pintype "output"))
      (node (ref "U2") (pin "6") (pinfunction "~{CTS}_6") (pintype "input"))
    )
    (net (code "52") (name "Net-(U4-FILTER)") (class "Default")
      (node (ref "C12") (pin "2") (pinfunction "2_2") (pintype "passive"))
      (node (ref "U4") (pin "1") (pinfunction "FILTER_1") (pintype "input"))
    )
    (net (code "53") (name "Net-(U5-CAPN)") (class "Default")
      (node (ref "C25") (pin "1") (pinfunction "1_1") (pintype "passive"))
      (node (ref "U5") (pin "19") (pinfunction "CAPN_19") (pintype "passive"))
    )
    (net (code "54") (name "Net-(U5-CAPP)") (class "Default")
      (node (ref "C25") (pin "2") (pinfunction "2_2") (pintype "passive"))
      (node (ref "U5") (pin "20") (pinfunction "CAPP_20") (pintype "passive"))
    )
    (net (code "55") (name "Net-(U5-CAPREG)") (class "Default")
      (node (ref "C34") (pin "2") (pinfunction "2_2") (pintype "passive"))
      (node (ref "U5") (pin "26") (pinfunction "CAPREG_26") (pintype "passive"))
    )
    (net (code "56") (name "Net-(U6-CCAP)") (class "Default")
      (node (ref "C29") (pin "2") (pinfunction "2_2") (pintype "passive"))
      (node (ref "U6") (pin "3") (pinfunction "CCAP_3") (pintype "passive"))
    )
    (net (code "57") (name "Net-(U6-OUT+)") (class "Default")
      (node (ref "C30") (pin "1") (pinfunction "1_1") (pintype "passive"))
      (node (ref "U6") (pin "6") (pinfunction "OUT+_6") (pintype "output"))
    )
    (net (code "58") (name "Net-(U6-OUT-)") (class "Default")
      (node (ref "C31") (pin "1") (pinfunction "1_1") (pintype "passive"))
      (node (ref "U6") (pin "7") (pinfunction "OUT-_7") (pintype "output"))
    )
    (net (code "59") (name "Net-(U7A-IN+)") (class "Default")
      (node (ref "R15") (pin "2") (pinfunction "2_2") (pintype "passive"))
      (node (ref "R17") (pin "1") (pinfunction "1_1") (pintype "passive"))
      (node (ref "U7") (pin "P$3") (pinfunction "IN+_P$3") (pintype "input"))
    )
    (net (code "60") (name "Net-(U7A-IN-)") (class "Default")
      (node (ref "R16") (pin "2") (pinfunction "2_2") (pintype "passive"))
      (node (ref "R18") (pin "1") (pinfunction "1_1") (pintype "passive"))
      (node (ref "U7") (pin "P$2") (pinfunction "IN-_P$2") (pintype "input"))
    )
    (net (code "61") (name "Net-(U7A-OUT)") (class "Default")
      (node (ref "C32") (pin "1") (pinfunction "1_1") (pintype "passive"))
      (node (ref "R18") (pin "2") (pinfunction "2_2") (pintype "passive"))
      (node (ref "U7") (pin "P$1") (pinfunction "OUT_P$1") (pintype "output"))
      (node (ref "U7") (pin "P$5") (pinfunction "IN+_P$5") (pintype "input"))
    )
    (net (code "62") (name "unconnected-(IC1-P1.0{slash}UCB0STE{slash}SMCLK{slash}COMP0.0{slash}A0{slash}VEREF+-Pad3)") (class "Default")
      (node (ref "IC1") (pin "3") (pinfunction "P1.0/UCB0STE/SMCLK/COMP0.0/A0/VEREF+_3") (pintype "bidirectional"))
    )
    (net (code "63") (name "unconnected-(IC1-P1.3{slash}UCB0SOMI{slash}UCB0SCL{slash}OA0+{slash}A3-Pad48)") (class "Default")
      (node (ref "IC1") (pin "48") (pinfunction "P1.3/UCB0SOMI/UCB0SCL/OA0+/A3_48") (pintype "bidirectional"))
    )
    (net (code "64") (name "unconnected-(IC1-P1.4{slash}UCA0STE{slash}TCK{slash}A4-Pad34)") (class "Default")
      (node (ref "IC1") (pin "34") (pinfunction "P1.4/UCA0STE/TCK/A4_34") (pintype "bidirectional"))
    )
    (net (code "65") (name "unconnected-(IC1-P1.5{slash}UCA0CLK{slash}TMS{slash}OA1O{slash}A5-Pad33)") (class "Default")
      (node (ref "IC1") (pin "33") (pinfunction "P1.5/UCA0CLK/TMS/OA1O/A5_33") (pintype "bidirectional"))
    )
    (net (code "66") (name "unconnected-(IC1-P1.6{slash}UCA0RXD{slash}UCA0SOMI{slash}TB0.1{slash}TDI{slash}TCLK{slash}OA1-{slash}A6-Pad32)") (class "Default")
      (node (ref "IC1") (pin "32") (pinfunction "P1.6/UCA0RXD/UCA0SOMI/TB0.1/TDI/TCLK/OA1-/A6_32") (pintype "bidirectional"))
    )
    (net (code "67") (name "unconnected-(IC1-P1.7{slash}UCA0TXD{slash}UCA0SIMO{slash}TB0.2{slash}TDO{slash}OA1+{slash}A7{slash}VREF+-Pad31)") (class "Default")
      (node (ref "IC1") (pin "31") (pinfunction "P1.7/UCA0TXD/UCA0SIMO/TB0.2/TDO/OA1+/A7/VREF+_31") (pintype "bidirectional"))
    )
    (net (code "68") (name "unconnected-(IC1-P2.0{slash}TB1.1{slash}COMP0.O-Pad30)") (class "Default")
      (node (ref "IC1") (pin "30") (pinfunction "P2.0/TB1.1/COMP0.O_30") (pintype "bidirectional"))
    )
    (net (code "69") (name "unconnected-(IC1-P2.1{slash}TB1.2{slash}COMP1.O-Pad29)") (class "Default")
      (node (ref "IC1") (pin "29") (pinfunction "P2.1/TB1.2/COMP1.O_29") (pintype "bidirectional"))
    )
    (net (code "70") (name "unconnected-(IC1-P2.2{slash}TB1CLK-Pad28)") (class "Default")
      (node (ref "IC1") (pin "28") (pinfunction "P2.2/TB1CLK_28") (pintype "bidirectional"))
    )
    (net (code "71") (name "unconnected-(IC1-P2.3{slash}TB1TRG-Pad27)") (class "Default")
      (node (ref "IC1") (pin "27") (pinfunction "P2.3/TB1TRG_27") (pintype "bidirectional"))
    )
    (net (code "72") (name "unconnected-(IC1-P2.4{slash}COMP1.1-Pad11)") (class "Default")
      (node (ref "IC1") (pin "11") (pinfunction "P2.4/COMP1.1_11") (pintype "bidirectional"))
    )
    (net (code "73") (name "unconnected-(IC1-P2.5{slash}COMP1.0-Pad10)") (class "Default")
      (node (ref "IC1") (pin "10") (pinfunction "P2.5/COMP1.0_10") (pintype "bidirectional"))
    )
    (net (code "74") (name "unconnected-(IC1-P2.6{slash}MCLK{slash}XOUT-Pad9)") (class "Default")
      (node (ref "IC1") (pin "9") (pinfunction "P2.6/MCLK/XOUT_9") (pintype "bidirectional"))
    )
    (net (code "75") (name "unconnected-(IC1-P2.7{slash}TB0CLK{slash}XIN-Pad8)") (class "Default")
      (node (ref "IC1") (pin "8") (pinfunction "P2.7/TB0CLK/XIN_8") (pintype "bidirectional"))
    )
    (net (code "76") (name "unconnected-(IC1-P3.0{slash}MCLK-Pad47)") (class "Default")
      (node (ref "IC1") (pin "47") (pinfunction "P3.0/MCLK_47") (pintype "bidirectional"))
    )
    (net (code "77") (name "unconnected-(IC1-P3.3{slash}OA2+-Pad44)") (class "Default")
      (node (ref "IC1") (pin "44") (pinfunction "P3.3/OA2+_44") (pintype "bidirectional"))
    )
    (net (code "78") (name "unconnected-(IC1-P3.4{slash}SMCLK-Pad38)") (class "Default")
      (node (ref "IC1") (pin "38") (pinfunction "P3.4/SMCLK_38") (pintype "bidirectional"))
    )
    (net (code "79") (name "unconnected-(IC1-P3.5{slash}OA3O-Pad37)") (class "Default")
      (node (ref "IC1") (pin "37") (pinfunction "P3.5/OA3O_37") (pintype "bidirectional"))
    )
    (net (code "80") (name "unconnected-(IC1-P3.7{slash}OA3+-Pad35)") (class "Default")
      (node (ref "IC1") (pin "35") (pinfunction "P3.7/OA3+_35") (pintype "bidirectional"))
    )
    (net (code "81") (name "unconnected-(IC1-P4.0{slash}UCA1STE{slash}ISOTXD{slash}ISORXD-Pad26)") (class "Default")
      (node (ref "IC1") (pin "26") (pinfunction "P4.0/UCA1STE/ISOTXD/ISORXD_26") (pintype "bidirectional"))
    )
    (net (code "82") (name "unconnected-(IC1-P4.1{slash}UCA1CLK-Pad25)") (class "Default")
      (node (ref "IC1") (pin "25") (pinfunction "P4.1/UCA1CLK_25") (pintype "bidirectional"))
    )
    (net (code "83") (name "unconnected-(IC1-P5.0{slash}TB2.1{slash}MFM.RX{slash}A8-Pad43)") (class "Default")
      (node (ref "IC1") (pin "43") (pinfunction "P5.0/TB2.1/MFM.RX/A8_43") (pintype "bidirectional"))
    )
    (net (code "84") (name "unconnected-(IC1-P5.1{slash}TB2.2{slash}MFM.TX{slash}A9-Pad42)") (class "Default")
      (node (ref "IC1") (pin "42") (pinfunction "P5.1/TB2.2/MFM.TX/A9_42") (pintype "bidirectional"))
    )
    (net (code "85") (name "unconnected-(IC1-P5.2{slash}TB2CLK{slash}A10-Pad41)") (class "Default")
      (node (ref "IC1") (pin "41") (pinfunction "P5.2/TB2CLK/A10_41") (pintype "bidirectional"))
    )
    (net (code "86") (name "unconnected-(IC1-P5.3{slash}TB2TRG{slash}A11-Pad40)") (class "Default")
      (node (ref "IC1") (pin "40") (pinfunction "P5.3/TB2TRG/A11_40") (pintype "bidirectional"))
    )
    (net (code "87") (name "unconnected-(IC1-P5.4-Pad39)") (class "Default")
      (node (ref "IC1") (pin "39") (pinfunction "P5.4_39") (pintype "bidirectional"))
    )
    (net (code "88") (name "unconnected-(IC1-P6.0{slash}TB3.1-Pad22)") (class "Default")
      (node (ref "IC1") (pin "22") (pinfunction "P6.0/TB3.1_22") (pintype "bidirectional"))
    )
    (net (code "89") (name "unconnected-(IC1-P6.1{slash}TB3.2-Pad21)") (class "Default")
      (node (ref "IC1") (pin "21") (pinfunction "P6.1/TB3.2_21") (pintype "bidirectional"))
    )
    (net (code "90") (name "unconnected-(IC1-P6.2{slash}TB3.3-Pad20)") (class "Default")
      (node (ref "IC1") (pin "20") (pinfunction "P6.2/TB3.3_20") (pintype "bidirectional"))
    )
    (net (code "91") (name "unconnected-(IC1-P6.3{slash}TB3.4-Pad19)") (class "Default")
      (node (ref "IC1") (pin "19") (pinfunction "P6.3/TB3.4_19") (pintype "bidirectional"))
    )
    (net (code "92") (name "unconnected-(IC1-P6.4{slash}TB3.5-Pad18)") (class "Default")
      (node (ref "IC1") (pin "18") (pinfunction "P6.4/TB3.5_18") (pintype "bidirectional"))
    )
    (net (code "93") (name "unconnected-(U1C-IN+-PadP$5)") (class "Default")
      (node (ref "U1") (pin "P$5") (pinfunction "IN+_P$5") (pintype "input"))
    )
    (net (code "94") (name "unconnected-(U1C-IN--PadP$6)") (class "Default")
      (node (ref "U1") (pin "P$6") (pinfunction "IN-_P$6") (pintype "input"))
    )
    (net (code "95") (name "unconnected-(U1C-OUT-PadP$7)") (class "Default")
      (node (ref "U1") (pin "P$7") (pinfunction "OUT_P$7") (pintype "output"))
    )
    (net (code "96") (name "unconnected-(U2-CBUS0-Pad15)") (class "Default")
      (node (ref "U2") (pin "15") (pinfunction "CBUS0_15") (pintype "bidirectional"))
    )
    (net (code "97") (name "unconnected-(U2-CBUS3-Pad16)") (class "Default")
      (node (ref "U2") (pin "16") (pinfunction "CBUS3_16") (pintype "bidirectional"))
    )
    (net (code "98") (name "unconnected-(U5-AIN4N-Pad15)") (class "Default")
      (node (ref "U5") (pin "15") (pinfunction "AIN4N_15") (pintype "input"))
    )
    (net (code "99") (name "unconnected-(U5-AIN4P-Pad16)") (class "Default")
      (node (ref "U5") (pin "16") (pinfunction "AIN4P_16") (pintype "input"))
    )
    (net (code "100") (name "unconnected-(U5-AIN5N-Pad17)") (class "Default")
      (node (ref "U5") (pin "17") (pinfunction "AIN5N_17") (pintype "input"))
    )
    (net (code "101") (name "unconnected-(U5-AIN5P-Pad18)") (class "Default")
      (node (ref "U5") (pin "18") (pinfunction "AIN5P_18") (pintype "input"))
    )
    (net (code "102") (name "unconnected-(U5-GPIO0{slash}CLK-Pad23)") (class "Default")
      (node (ref "U5") (pin "23") (pinfunction "GPIO0/CLK_23") (pintype "bidirectional"))
    )
    (net (code "103") (name "unconnected-(U5-GPIO1{slash}SYNC-Pad25)") (class "Default")
      (node (ref "U5") (pin "25") (pinfunction "GPIO1/SYNC_25") (pintype "bidirectional"))
    )
    (net (code "104") (name "unconnected-(U5-GPO0-Pad24)") (class "Default")
      (node (ref "U5") (pin "24") (pinfunction "GPO0_24") (pintype "bidirectional"))
    )
    (net (code "105") (name "unconnected-(U5-GPO1-Pad22)") (class "Default")
      (node (ref "U5") (pin "22") (pinfunction "GPO1_22") (pintype "bidirectional"))
    )
    (net (code "106") (name "unconnected-(USB1-ID-PadP$4)") (class "Default")
      (node (ref "USB1") (pin "P$4") (pinfunction "ID_P$4") (pintype "bidirectional"))
    )
  )
)
